# 5__Power_Supply.net
KiCad netlist of a schematic drawn in Altium Designer
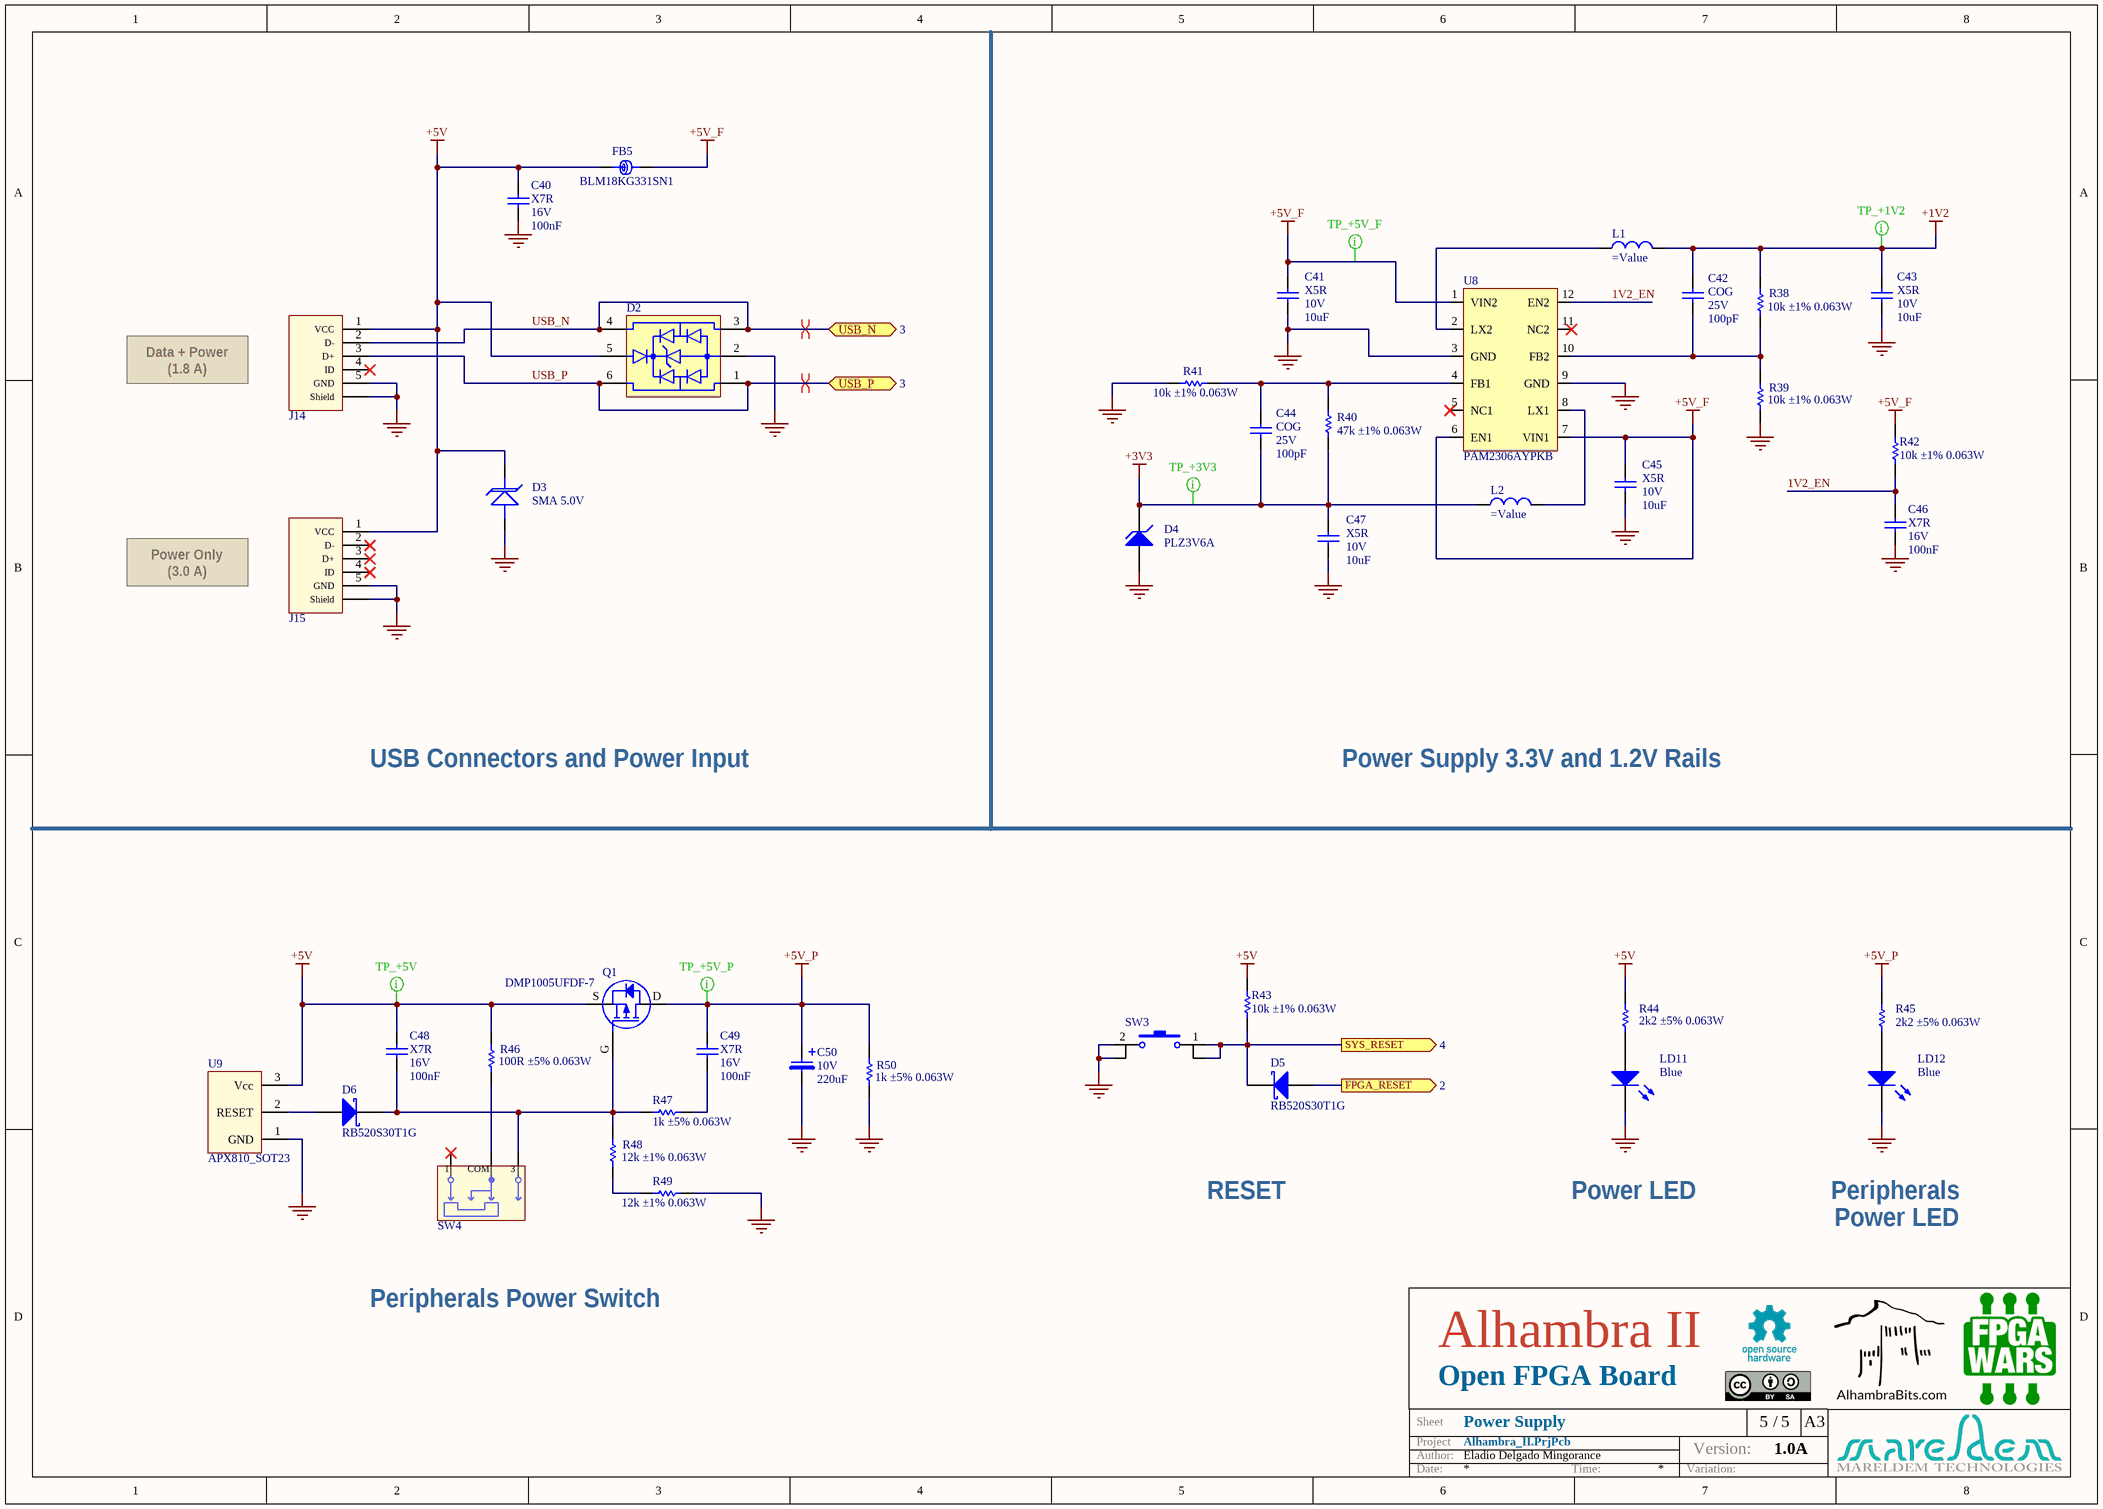
[diagram p0: [5]_Power_Supply.SchDoc]

(export (version "E")
  (design (tool "Eeschema 10.0.6"))
  (components
    (comp (ref "C40")
      (value "Capacitor")
      (footprint "C0402")
      (description "Capacitor SMD")
      (fields
        (field (name "DIELECTRIC") "X7R")
        (field (name "VOLTAGE") "16V")
        (field (name "CAPACITANCE") "100nF")
        (field (name "PART NUMBER") "C0402_100nF_16V_±10%")
        (field (name "TOLERANCE") "±10%")
      )
      (libsource (lib "Pasives_Capacitor_SMD") (part "Capacitor"))
    )
    (comp (ref "C41")
      (value "Capacitor")
      (footprint "C0805_1.25_HD")
      (description "Capacitor SMD")
      (fields
        (field (name "DIELECTRIC") "X5R")
        (field (name "VOLTAGE") "10V")
        (field (name "CAPACITANCE") "10uF")
        (field (name "PART NUMBER") "C0805_1.25_HD_10uF_10V_X5R")
        (field (name "TOLERANCE") "±10%")
      )
      (libsource (lib "") (part "Capacitor_1"))
    )
    (comp (ref "C42")
      (value "Capacitor")
      (footprint "C0402")
      (description "Capacitor SMD")
      (fields
        (field (name "DIELECTRIC") "COG")
        (field (name "VOLTAGE") "25V")
        (field (name "CAPACITANCE") "100pF")
        (field (name "PART NUMBER") "C0402_100pF_25V_±5%")
        (field (name "TOLERANCE") "±5%")
      )
      (libsource (lib "") (part "Capacitor_1"))
    )
    (comp (ref "C43")
      (value "Capacitor")
      (footprint "C0603")
      (description "Capacitor SMD")
      (fields
        (field (name "DIELECTRIC") "X5R")
        (field (name "VOLTAGE") "10V")
        (field (name "CAPACITANCE") "10uF")
        (field (name "PART NUMBER") "C0603_10uF_10V_±10%")
        (field (name "TOLERANCE") "±10%")
      )
      (libsource (lib "") (part "Capacitor_1"))
    )
    (comp (ref "C44")
      (value "Capacitor")
      (footprint "C0402")
      (description "Capacitor SMD")
      (fields
        (field (name "DIELECTRIC") "COG")
        (field (name "VOLTAGE") "25V")
        (field (name "CAPACITANCE") "100pF")
        (field (name "PART NUMBER") "C0402_100pF_25V_±5%")
        (field (name "TOLERANCE") "±5%")
      )
      (libsource (lib "") (part "Capacitor_1"))
    )
    (comp (ref "C45")
      (value "Capacitor")
      (footprint "C0805_1.25_HD")
      (description "Capacitor SMD")
      (fields
        (field (name "DIELECTRIC") "X5R")
        (field (name "VOLTAGE") "10V")
        (field (name "CAPACITANCE") "10uF")
        (field (name "PART NUMBER") "C0805_1.25_HD_10uF_10V_X5R")
        (field (name "TOLERANCE") "±10%")
      )
      (libsource (lib "") (part "Capacitor_1"))
    )
    (comp (ref "C46")
      (value "Capacitor")
      (footprint "C0402")
      (description "Capacitor SMD")
      (fields
        (field (name "DIELECTRIC") "X7R")
        (field (name "VOLTAGE") "16V")
        (field (name "CAPACITANCE") "100nF")
        (field (name "PART NUMBER") "C0402_100nF_16V_±10%")
        (field (name "TOLERANCE") "±10%")
      )
      (libsource (lib "Pasives_Capacitor_SMD") (part "Capacitor"))
    )
    (comp (ref "C47")
      (value "Capacitor")
      (footprint "C0805_1.25_HD")
      (description "Capacitor SMD")
      (fields
        (field (name "DIELECTRIC") "X5R")
        (field (name "VOLTAGE") "10V")
        (field (name "CAPACITANCE") "10uF")
        (field (name "PART NUMBER") "C0805_1.25_HD_10uF_10V_X5R")
        (field (name "TOLERANCE") "±10%")
      )
      (libsource (lib "") (part "Capacitor_1"))
    )
    (comp (ref "C48")
      (value "Capacitor")
      (footprint "C0402")
      (description "Capacitor SMD")
      (fields
        (field (name "DIELECTRIC") "X7R")
        (field (name "VOLTAGE") "16V")
        (field (name "CAPACITANCE") "100nF")
        (field (name "PART NUMBER") "C0402_100nF_16V_±10%")
        (field (name "TOLERANCE") "±10%")
      )
      (libsource (lib "Pasives_Capacitor_SMD") (part "Capacitor"))
    )
    (comp (ref "C49")
      (value "Capacitor")
      (footprint "C0402")
      (description "Capacitor SMD")
      (fields
        (field (name "DIELECTRIC") "X7R")
        (field (name "VOLTAGE") "16V")
        (field (name "CAPACITANCE") "100nF")
        (field (name "PART NUMBER") "C0402_100nF_16V_±10%")
        (field (name "TOLERANCE") "±10%")
      )
      (libsource (lib "Pasives_Capacitor_SMD") (part "Capacitor"))
    )
    (comp (ref "C50")
      (value "Electrolytic")
      (footprint "C_POL_6.3x5.8_WE")
      (description "Capacitor, Electrolytic, SMD")
      (fields
        (field (name "VOLTAGE") "10V")
        (field (name "CAPACITANCE") "220uF")
        (field (name "PART NUMBER") "Cap_Al_220uF_10V")
        (field (name "MANUFACTURER") "WE")
      )
      (libsource (lib "Pasives_Electrolytic_SMD") (part "Electrolytic"))
    )
    (comp (ref "D2")
      (value "ESDUSB")
      (footprint "SOT563")
      (description "Protection, USB ESD")
      (fields (field (name "PART NUMBER") "USB ESD Single") (field (name "MANUFACTURER") "Würth"))
      (libsource (lib "Protection") (part "ESDUSB"))
    )
    (comp (ref "D3")
      (value "SMA 5.0V")
      (footprint "DO-214AC-SMA_Unidir")
      (description "Protection, Transient Suppression Diode")
      (fields (field (name "PART NUMBER") "TVS 5Vdc Unidir SMA") (field (name "VOLTAGE") "5Vdc"))
      (libsource (lib "Protection") (part "Zener_TVS"))
    )
    (comp (ref "D4")
      (value "PLZ3V6A")
      (footprint "DO-219AC")
      (description "Zener Diode")
      (fields (field (name "TOLERANCE") "0,025") (field (name "POWER") "500mW"))
      (libsource (lib "Diodes") (part "Zener"))
    )
    (comp (ref "D5")
      (value "RB520S30T1G")
      (footprint "SOD523")
      (description "Schottky Diode")
      (fields (field (name "MANUFACTURER") "On Semiconductor"))
      (libsource (lib "Diodes") (part "Schottky"))
    )
    (comp (ref "D6")
      (value "RB520S30T1G")
      (footprint "SOD523")
      (description "Schottky Diode")
      (fields (field (name "MANUFACTURER") "On Semiconductor"))
      (libsource (lib "Diodes") (part "Schottky"))
    )
    (comp (ref "FB5")
      (value "BLM18KG331SN1")
      (footprint "L0603")
      (description "Ferrite Bead")
      (fields (field (name "PART NUMBER") "L0603_330R_0,080R_1700 mA") (field (name "MANUFACTURER") "Murata"))
      (libsource (lib "Pasives_Inductor_SMD") (part "Ferrite Bead"))
    )
    (comp (ref "J14")
      (value "629105136821")
      (footprint "629105136821")
      (description "Micro USB 2.0 SMT Type B Horizontal 5 Contacts WR-COM")
      (fields
        (field (name "PART NUMBER") "Micro USB 1.8A WE")
        (field (name "MANUFACTURER") "WE")
        (field (name "PUBLISHER") "Wurth Elektronik")
      )
      (libsource (lib "Connector_USB") (part "629105136821"))
    )
    (comp (ref "J15")
      (value "629105150521")
      (footprint "629105150521")
      (description "Micro USB 2.0 SMT Type B Horizontal 5 Contacts High Current WR-COM")
      (fields
        (field (name "PART NUMBER") "Micro USB 3.0A WE")
        (field (name "MANUFACTURER") "WE")
        (field (name "PUBLISHER") "Wurth Elektronik")
      )
      (libsource (lib "Connector_USB") (part "629105150521"))
    )
    (comp (ref "L1")
      (value "~")
      (footprint "4018_WE_LQS_4R7")
      (description "Inductor SMD")
      (fields (field (name "PART NUMBER") "4,7uH_1,7A_4018") (field (name "MANUFACTURER") "WE"))
      (libsource (lib "Pasives_Inductor_SMD") (part "Inductor"))
    )
    (comp (ref "L2")
      (value "~")
      (footprint "4018_WE_LQS_4R7")
      (description "Inductor SMD")
      (fields (field (name "PART NUMBER") "4,7uH_1,7A_4018") (field (name "MANUFACTURER") "WE"))
      (libsource (lib "Pasives_Inductor_SMD") (part "Inductor"))
    )
    (comp (ref "LD11")
      (value "Blue")
      (footprint "LED0603")
      (description "LED")
      (fields (field (name "PART NUMBER") "LED Blue 0603 Wurth") (field (name "MANUFACTURER") "WE"))
      (libsource (lib "Optoelectronics") (part "LED"))
    )
    (comp (ref "LD12")
      (value "Blue")
      (footprint "LED0603")
      (description "LED")
      (fields (field (name "PART NUMBER") "LED Blue 0603 Wurth") (field (name "MANUFACTURER") "WE"))
      (libsource (lib "Optoelectronics") (part "LED"))
    )
    (comp (ref "Q1")
      (value "DMP1005UFDF-7")
      (footprint "U-DFN2020-6")
      (description "P-Channel MOSFET")
      (fields (field (name "PART NUMBER") "DMP1005UFDF") (field (name "MANUFACTURER") "Diodes Incorporated"))
      (libsource (lib "Transistors") (part "Mosfet_P_3pin"))
    )
    (comp (ref "R38")
      (value "10k ±1% 0.063W")
      (footprint "R0402")
      (description "Resistor, SMD")
      (fields (field (name "TOLERANCE") "±1%") (field (name "POWER") "0.063W"))
      (libsource (lib "Pasives_Resistor_SMD") (part "Resistor"))
    )
    (comp (ref "R39")
      (value "10k ±1% 0.063W")
      (footprint "R0402")
      (description "Resistor, SMD")
      (fields (field (name "TOLERANCE") "±1%") (field (name "POWER") "0.063W"))
      (libsource (lib "Pasives_Resistor_SMD") (part "Resistor"))
    )
    (comp (ref "R40")
      (value "47k ±1% 0.063W")
      (footprint "R0402")
      (description "Resistor, SMD")
      (fields (field (name "TOLERANCE") "±1%") (field (name "POWER") "0.063W"))
      (libsource (lib "Pasives_Resistor_SMD") (part "Resistor"))
    )
    (comp (ref "R41")
      (value "10k ±1% 0.063W")
      (footprint "R0402")
      (description "Resistor, SMD")
      (fields (field (name "TOLERANCE") "±1%") (field (name "POWER") "0.063W"))
      (libsource (lib "Pasives_Resistor_SMD") (part "Resistor"))
    )
    (comp (ref "R42")
      (value "10k ±1% 0.063W")
      (footprint "R0402")
      (description "Resistor, SMD")
      (fields (field (name "TOLERANCE") "±1%") (field (name "POWER") "0.063W"))
      (libsource (lib "Pasives_Resistor_SMD") (part "Resistor"))
    )
    (comp (ref "R43")
      (value "10k ±1% 0.063W")
      (footprint "R0402")
      (description "Resistor, SMD")
      (fields (field (name "TOLERANCE") "±1%") (field (name "POWER") "0.063W"))
      (libsource (lib "Pasives_Resistor_SMD") (part "Resistor"))
    )
    (comp (ref "R44")
      (value "2k2 ±5% 0.063W")
      (footprint "R0402")
      (description "Resistor, SMD")
      (fields (field (name "TOLERANCE") "±5%") (field (name "POWER") "0.063W"))
      (libsource (lib "Pasives_Resistor_SMD") (part "Resistor"))
    )
    (comp (ref "R45")
      (value "2k2 ±5% 0.063W")
      (footprint "R0402")
      (description "Resistor, SMD")
      (fields (field (name "TOLERANCE") "±5%") (field (name "POWER") "0.063W"))
      (libsource (lib "Pasives_Resistor_SMD") (part "Resistor"))
    )
    (comp (ref "R46")
      (value "100R ±5% 0.063W")
      (footprint "R0402")
      (description "Resistor, SMD")
      (fields (field (name "TOLERANCE") "±5%") (field (name "POWER") "0.063W"))
      (libsource (lib "Pasives_Resistor_SMD") (part "Resistor"))
    )
    (comp (ref "R47")
      (value "1k ±5% 0.063W")
      (footprint "R0402")
      (description "Resistor, SMD")
      (fields (field (name "TOLERANCE") "±5%") (field (name "POWER") "0.063W"))
      (libsource (lib "Pasives_Resistor_SMD") (part "Resistor"))
    )
    (comp (ref "R48")
      (value "12k ±1% 0.063W")
      (footprint "R0402")
      (description "Resistor, SMD")
      (fields (field (name "TOLERANCE") "±1%") (field (name "POWER") "0.063W"))
      (libsource (lib "Pasives_Resistor_SMD") (part "Resistor"))
    )
    (comp (ref "R49")
      (value "12k ±1% 0.063W")
      (footprint "R0402")
      (description "Resistor, SMD")
      (fields (field (name "TOLERANCE") "±1%") (field (name "POWER") "0.063W"))
      (libsource (lib "Pasives_Resistor_SMD") (part "Resistor"))
    )
    (comp (ref "R50")
      (value "1k ±5% 0.063W")
      (footprint "R0402")
      (description "Resistor, SMD")
      (fields (field (name "TOLERANCE") "±5%") (field (name "POWER") "0.063W"))
      (libsource (lib "Pasives_Resistor_SMD") (part "Resistor"))
    )
    (comp (ref "SW3")
      (value "Switch_4P_SP_1-3_4-2")
      (footprint "4363x30458xx")
      (description "Micro miniature pushbutton surface Switch")
      (fields (field (name "PART NUMBER") "SW 4,7x3,5 mm SMD side push") (field (name "MANUFACTURER") "WE"))
      (libsource (lib "Electromechanical") (part "Switch_4P_SP_1-3_4-2"))
    )
    (comp (ref "SW4")
      (value "450404015514")
      (footprint "450404015514")
      (description "WS-SLSU 6.7x2.7 mm SMD Right Angled, boss design")
      (fields
        (field (name "PART NUMBER") "RA Slide Switch")
        (field (name "MANUFACTURER") "WE")
        (field (name "PUBLISHER") "Wurth Elektronik")
      )
      (libsource (lib "Electromechanical") (part "450404015514"))
    )
    (comp (ref "U8")
      (value "PAM2306AYPKB")
      (footprint "WDFN_12_3x3")
      (description "Dual Step-Down DC/DC converter 1A, 1.5 MHz")
      (fields (field (name "PART NUMBER") "PAM2360") (field (name "MANUFACTURER") "Diodes"))
      (libsource (lib "Power_Regulator") (part "PAM2306"))
    )
    (comp (ref "U9")
      (value "APX810_SOT23")
      (footprint "SOT23-3")
      (description "Voltage supervisor, Reset active high, 200ms")
      (fields (field (name "PART NUMBER") "APX810") (field (name "MANUFACTURER") "Diodes Incorporated"))
      (libsource (lib "Power_Supervisor") (part "APX810_SOT23"))
    )
  )
  (nets
    (net (code "1") (name "+1V2") (class "Default")
      (node (ref "C42") (pin "2") (pinfunction "2_2") (pintype "passive"))
      (node (ref "C43") (pin "2") (pinfunction "2_2") (pintype "passive"))
      (node (ref "L1") (pin "1") (pinfunction "1_1") (pintype "passive"))
      (node (ref "R38") (pin "2") (pinfunction "2_2") (pintype "passive"))
    )
    (net (code "2") (name "+3V3") (class "Default")
      (node (ref "C44") (pin "1") (pinfunction "1_1") (pintype "passive"))
      (node (ref "C47") (pin "2") (pinfunction "2_2") (pintype "passive"))
      (node (ref "D4") (pin "k") (pinfunction "K_k") (pintype "passive"))
      (node (ref "L2") (pin "2") (pinfunction "2_2") (pintype "passive"))
      (node (ref "R40") (pin "1") (pinfunction "1_1") (pintype "passive"))
    )
    (net (code "3") (name "+5V") (class "Default")
      (node (ref "C40") (pin "2") (pinfunction "2_2") (pintype "passive"))
      (node (ref "C48") (pin "2") (pinfunction "2_2") (pintype "passive"))
      (node (ref "D2") (pin "5") (pinfunction "5_5") (pintype "passive"))
      (node (ref "D3") (pin "K") (pinfunction "K_K") (pintype "passive"))
      (node (ref "FB5") (pin "1") (pinfunction "1_1") (pintype "passive"))
      (node (ref "J14") (pin "1") (pinfunction "VCC_1") (pintype "passive"))
      (node (ref "J15") (pin "1") (pinfunction "VCC_1") (pintype "passive"))
      (node (ref "Q1") (pin "S") (pinfunction "S_S") (pintype "passive"))
      (node (ref "R43") (pin "2") (pinfunction "2_2") (pintype "passive"))
      (node (ref "R44") (pin "2") (pinfunction "2_2") (pintype "passive"))
      (node (ref "R46") (pin "2") (pinfunction "2_2") (pintype "passive"))
      (node (ref "U9") (pin "3") (pinfunction "Vcc_3") (pintype "passive"))
    )
    (net (code "4") (name "+5V_F") (class "Default")
      (node (ref "C41") (pin "2") (pinfunction "2_2") (pintype "passive"))
      (node (ref "C45") (pin "2") (pinfunction "2_2") (pintype "passive"))
      (node (ref "FB5") (pin "2") (pinfunction "2_2") (pintype "passive"))
      (node (ref "R42") (pin "2") (pinfunction "2_2") (pintype "passive"))
      (node (ref "U8") (pin "1") (pinfunction "VIN2_1") (pintype "passive"))
      (node (ref "U8") (pin "6") (pinfunction "EN1_6") (pintype "passive"))
      (node (ref "U8") (pin "7") (pinfunction "VIN1_7") (pintype "passive"))
    )
    (net (code "5") (name "+5V_P") (class "Default")
      (node (ref "C49") (pin "2") (pinfunction "2_2") (pintype "passive"))
      (node (ref "C50") (pin "1") (pinfunction "1_1") (pintype "passive"))
      (node (ref "Q1") (pin "D") (pinfunction "D_D") (pintype "passive"))
      (node (ref "R45") (pin "2") (pinfunction "2_2") (pintype "passive"))
      (node (ref "R50") (pin "2") (pinfunction "2_2") (pintype "passive"))
    )
    (net (code "6") (name "/1V2_EN") (class "Default")
      (node (ref "C46") (pin "2") (pinfunction "2_2") (pintype "passive"))
      (node (ref "R42") (pin "1") (pinfunction "1_1") (pintype "passive"))
      (node (ref "U8") (pin "12") (pinfunction "EN2_12") (pintype "passive"))
    )
    (net (code "7") (name "/FPGA_RESET") (class "Default")
      (node (ref "D5") (pin "A") (pinfunction "A_A") (pintype "passive"))
    )
    (net (code "8") (name "/SYS_RESET") (class "Default")
      (node (ref "D5") (pin "k") (pinfunction "K_k") (pintype "passive"))
      (node (ref "R43") (pin "1") (pinfunction "1_1") (pintype "passive"))
      (node (ref "SW3") (pin "1") (pinfunction "1_1") (pintype "passive"))
      (node (ref "SW3") (pin "3") (pinfunction "3_3") (pintype "passive"))
    )
    (net (code "9") (name "/USB_N") (class "Default")
      (node (ref "D2") (pin "3") (pinfunction "3_3") (pintype "passive"))
      (node (ref "D2") (pin "4") (pinfunction "4_4") (pintype "passive"))
      (node (ref "J14") (pin "2") (pinfunction "D-_2") (pintype "passive"))
    )
    (net (code "10") (name "/USB_P") (class "Default")
      (node (ref "D2") (pin "1") (pinfunction "1_1") (pintype "passive"))
      (node (ref "D2") (pin "6") (pinfunction "6_6") (pintype "passive"))
      (node (ref "J14") (pin "3") (pinfunction "D+_3") (pintype "passive"))
    )
    (net (code "11") (name "GND") (class "Default")
      (node (ref "C40") (pin "1") (pinfunction "1_1") (pintype "passive"))
      (node (ref "C41") (pin "1") (pinfunction "1_1") (pintype "passive"))
      (node (ref "C43") (pin "1") (pinfunction "1_1") (pintype "passive"))
      (node (ref "C45") (pin "1") (pinfunction "1_1") (pintype "passive"))
      (node (ref "C46") (pin "1") (pinfunction "1_1") (pintype "passive"))
      (node (ref "C47") (pin "1") (pinfunction "1_1") (pintype "passive"))
      (node (ref "C50") (pin "2") (pinfunction "2_2") (pintype "passive"))
      (node (ref "D2") (pin "2") (pinfunction "2_2") (pintype "passive"))
      (node (ref "D3") (pin "A") (pinfunction "A_A") (pintype "passive"))
      (node (ref "D4") (pin "A") (pinfunction "A_A") (pintype "passive"))
      (node (ref "J14") (pin "5") (pinfunction "GND_5") (pintype "passive"))
      (node (ref "J14") (pin "Shell") (pinfunction "Shield_Shell") (pintype "passive"))
      (node (ref "J15") (pin "5") (pinfunction "GND_5") (pintype "passive"))
      (node (ref "J15") (pin "Shell") (pinfunction "Shield_Shell") (pintype "passive"))
      (node (ref "LD11") (pin "K") (pinfunction "K_K") (pintype "passive"))
      (node (ref "LD12") (pin "K") (pinfunction "K_K") (pintype "passive"))
      (node (ref "R39") (pin "1") (pinfunction "1_1") (pintype "passive"))
      (node (ref "R41") (pin "1") (pinfunction "1_1") (pintype "passive"))
      (node (ref "R49") (pin "2") (pinfunction "2_2") (pintype "passive"))
      (node (ref "R50") (pin "1") (pinfunction "1_1") (pintype "passive"))
      (node (ref "SW3") (pin "2") (pinfunction "2_2") (pintype "passive"))
      (node (ref "SW3") (pin "4") (pinfunction "4_4") (pintype "passive"))
      (node (ref "U8") (pin "3") (pinfunction "GND_3") (pintype "passive"))
      (node (ref "U8") (pin "9") (pinfunction "GND_9") (pintype "passive"))
      (node (ref "U9") (pin "1") (pinfunction "GND_1") (pintype "passive"))
    )
    (net (code "12") (name "Net-(C49-Pad1)") (class "Default")
      (node (ref "C49") (pin "1") (pinfunction "1_1") (pintype "passive"))
      (node (ref "R47") (pin "2") (pinfunction "2_2") (pintype "passive"))
    )
    (net (code "13") (name "Net-(D6-K)") (class "Default")
      (node (ref "C48") (pin "1") (pinfunction "1_1") (pintype "passive"))
      (node (ref "D6") (pin "k") (pinfunction "K_k") (pintype "passive"))
      (node (ref "Q1") (pin "G") (pinfunction "G_G") (pintype "passive"))
      (node (ref "R47") (pin "1") (pinfunction "1_1") (pintype "passive"))
      (node (ref "R48") (pin "1") (pinfunction "1_1") (pintype "passive"))
      (node (ref "SW4") (pin "3") (pinfunction "3_3") (pintype "passive"))
    )
    (net (code "14") (name "Net-(LD11-PadA)") (class "Default")
      (node (ref "LD11") (pin "A") (pinfunction "A_A") (pintype "passive"))
      (node (ref "R44") (pin "1") (pinfunction "1_1") (pintype "passive"))
    )
    (net (code "15") (name "Net-(LD12-PadA)") (class "Default")
      (node (ref "LD12") (pin "A") (pinfunction "A_A") (pintype "passive"))
      (node (ref "R45") (pin "1") (pinfunction "1_1") (pintype "passive"))
    )
    (net (code "16") (name "Net-(R48-Pad2)") (class "Default")
      (node (ref "R48") (pin "2") (pinfunction "2_2") (pintype "passive"))
      (node (ref "R49") (pin "1") (pinfunction "1_1") (pintype "passive"))
    )
    (net (code "17") (name "Net-(SW4-COM)") (class "Default")
      (node (ref "R46") (pin "1") (pinfunction "1_1") (pintype "passive"))
      (node (ref "SW4") (pin "2") (pinfunction "COM_2") (pintype "passive"))
    )
    (net (code "18") (name "Net-(U8-FB1)") (class "Default")
      (node (ref "C44") (pin "2") (pinfunction "2_2") (pintype "passive"))
      (node (ref "R40") (pin "2") (pinfunction "2_2") (pintype "passive"))
      (node (ref "R41") (pin "2") (pinfunction "2_2") (pintype "passive"))
      (node (ref "U8") (pin "4") (pinfunction "FB1_4") (pintype "passive"))
    )
    (net (code "19") (name "Net-(U8-FB2)") (class "Default")
      (node (ref "C42") (pin "1") (pinfunction "1_1") (pintype "passive"))
      (node (ref "R38") (pin "1") (pinfunction "1_1") (pintype "passive"))
      (node (ref "R39") (pin "2") (pinfunction "2_2") (pintype "passive"))
      (node (ref "U8") (pin "10") (pinfunction "FB2_10") (pintype "passive"))
    )
    (net (code "20") (name "Net-(U8-LX1)") (class "Default")
      (node (ref "L2") (pin "1") (pinfunction "1_1") (pintype "passive"))
      (node (ref "U8") (pin "8") (pinfunction "LX1_8") (pintype "passive"))
    )
    (net (code "21") (name "Net-(U8-LX2)") (class "Default")
      (node (ref "L1") (pin "2") (pinfunction "2_2") (pintype "passive"))
      (node (ref "U8") (pin "2") (pinfunction "LX2_2") (pintype "passive"))
    )
    (net (code "22") (name "Net-(U9-RESET)") (class "Default")
      (node (ref "D6") (pin "A") (pinfunction "A_A") (pintype "passive"))
      (node (ref "U9") (pin "2") (pinfunction "RESET_2") (pintype "passive"))
    )
    (net (code "23") (name "unconnected-(J14-ID-Pad4)") (class "Default")
      (node (ref "J14") (pin "4") (pinfunction "ID_4") (pintype "passive+no_connect"))
    )
    (net (code "24") (name "unconnected-(J15-D+-Pad3)") (class "Default")
      (node (ref "J15") (pin "3") (pinfunction "D+_3") (pintype "passive+no_connect"))
    )
    (net (code "25") (name "unconnected-(J15-D--Pad2)") (class "Default")
      (node (ref "J15") (pin "2") (pinfunction "D-_2") (pintype "passive+no_connect"))
    )
    (net (code "26") (name "unconnected-(J15-ID-Pad4)") (class "Default")
      (node (ref "J15") (pin "4") (pinfunction "ID_4") (pintype "passive+no_connect"))
    )
    (net (code "27") (name "unconnected-(SW4-Pad1)") (class "Default")
      (node (ref "SW4") (pin "1") (pinfunction "1_1") (pintype "passive+no_connect"))
    )
    (net (code "28") (name "unconnected-(U8-NC1-Pad5)") (class "Default")
      (node (ref "U8") (pin "5") (pinfunction "NC1_5") (pintype "passive+no_connect"))
    )
    (net (code "29") (name "unconnected-(U8-NC2-Pad11)") (class "Default")
      (node (ref "U8") (pin "11") (pinfunction "NC2_11") (pintype "passive+no_connect"))
    )
  )
)
